# 2_MCU.net
KiCad netlist of a schematic drawn in Altium Designer
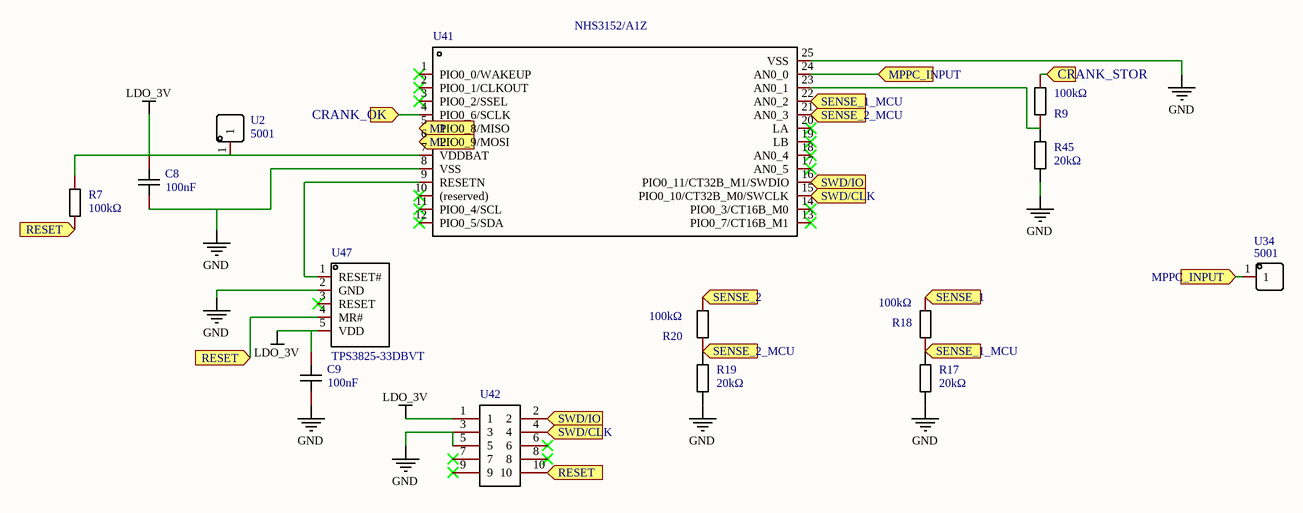
[diagram p0: 2_MCU.schdoc]

(export (version "E")
  (design (tool "Eeschema 10.0.6"))
  (components
    (comp (ref "C8")
      (value "100nF")
      (fields
        (field (name "NAME") "100nF")
        (field (name "MANUFACTURER") "YAGEO")
        (field (name "MANUFACTURER PART") "CC0603KRX7R9BB104")
      )
      (libsource (lib "altium-import") (part "root_3_CC0603KRX7R9BB104_"))
    )
    (comp (ref "C9")
      (value "100nF")
      (fields
        (field (name "NAME") "100nF")
        (field (name "MANUFACTURER") "YAGEO")
        (field (name "MANUFACTURER PART") "CC0603KRX7R9BB104")
      )
      (libsource (lib "altium-import") (part "root_3_CC0603KRX7R9BB104_"))
    )
    (comp (ref "R7")
      (value "100kΩ")
      (fields
        (field (name "MANUFACTURER") "UNI-ROYAL(厚声)")
        (field (name "MANUFACTURER PART") "0603WAF1003T5E")
        (field (name "TOLERANCE") "±1%")
      )
      (libsource (lib "altium-import") (part "root_3_0603WAF1003T5E_"))
    )
    (comp (ref "R9")
      (value "100kΩ")
      (fields
        (field (name "MANUFACTURER") "UNI-ROYAL(厚声)")
        (field (name "MANUFACTURER PART") "0603WAF1003T5E")
        (field (name "TOLERANCE") "±1%")
      )
      (libsource (lib "altium-import") (part "root_1_0603WAF1003T5E_"))
    )
    (comp (ref "R17")
      (value "20kΩ")
      (fields
        (field (name "NAME") "20kΩ")
        (field (name "MANUFACTURER") "UniOhm")
        (field (name "MANUFACTURER PART") "0603WAF2002T5E")
      )
      (libsource (lib "altium-import") (part "root_3_0603WAF2002T5E_"))
    )
    (comp (ref "R18")
      (value "100kΩ")
      (fields
        (field (name "MANUFACTURER") "UNI-ROYAL(厚声)")
        (field (name "MANUFACTURER PART") "0603WAF1003T5E")
        (field (name "TOLERANCE") "±1%")
      )
      (libsource (lib "altium-import") (part "root_1_0603WAF1003T5E_"))
    )
    (comp (ref "R19")
      (value "20kΩ")
      (fields
        (field (name "NAME") "20kΩ")
        (field (name "MANUFACTURER") "UniOhm")
        (field (name "MANUFACTURER PART") "0603WAF2002T5E")
      )
      (libsource (lib "altium-import") (part "root_3_0603WAF2002T5E_"))
    )
    (comp (ref "R20")
      (value "100kΩ")
      (fields
        (field (name "MANUFACTURER") "UNI-ROYAL(厚声)")
        (field (name "MANUFACTURER PART") "0603WAF1003T5E")
        (field (name "TOLERANCE") "±1%")
      )
      (libsource (lib "altium-import") (part "root_1_0603WAF1003T5E_"))
    )
    (comp (ref "R45")
      (value "20kΩ")
      (fields
        (field (name "NAME") "20kΩ")
        (field (name "MANUFACTURER") "UniOhm")
        (field (name "MANUFACTURER PART") "0603WAF2002T5E")
      )
      (libsource (lib "altium-import") (part "root_3_0603WAF2002T5E_"))
    )
    (comp (ref "U2")
      (value "5001")
      (fields (field (name "NAME") "5001") (field (name "MANUFACTURER") "Keystone"))
      (libsource (lib "altium-import") (part "root_1_5001_"))
    )
    (comp (ref "U34")
      (value "5001")
      (fields (field (name "NAME") "5001") (field (name "MANUFACTURER") "Keystone"))
      (libsource (lib "altium-import") (part "root_0_5001_"))
    )
    (comp (ref "U41")
      (value "NHS3152/A1Z")
      (fields (field (name "MANUFACTURER") "NXP(恩智浦)") (field (name "MANUFACTURER PART") "NHS3152/A1Z"))
      (libsource (lib "altium-import") (part "root_0_NHS3152/A1Z_"))
    )
    (comp (ref "U42")
      (value "20021121-00010T4LF")
      (fields (field (name "MANUFACTURER") "Amphenol"))
      (libsource (lib "altium-import") (part "root_3_20021121-00010T4LF_"))
    )
    (comp (ref "U47")
      (value "TPS3825-33DBVT")
      (fields (field (name "MANUFACTURER") "TI(德州仪器)") (field (name "MANUFACTURER PART") "TPS3825-33DBVT"))
      (libsource (lib "altium-import") (part "root_0_TPS3825-33DBVT_"))
    )
  )
  (nets
    (net (code "1") (name "/CRANK_OK") (class "Default")
      (node (ref "U41") (pin "4") (pinfunction "PIO0_6/SCLK_4") (pintype "passive"))
    )
    (net (code "2") (name "/CRANK_STOR") (class "Default")
      (node (ref "R9") (pin "2") (pinfunction "2_2") (pintype "passive"))
    )
    (net (code "3") (name "/M1") (class "Default")
      (node (ref "U41") (pin "5") (pinfunction "PIO0_8/MISO_5") (pintype "passive"))
    )
    (net (code "4") (name "/M2") (class "Default")
      (node (ref "U41") (pin "6") (pinfunction "PIO0_9/MOSI_6") (pintype "passive"))
    )
    (net (code "5") (name "/MPPC_INPUT") (class "Default")
      (node (ref "U34") (pin "1") (pinfunction "1_1") (pintype "passive"))
      (node (ref "U41") (pin "24") (pinfunction "AN0_0_24") (pintype "passive"))
    )
    (net (code "6") (name "/RESET") (class "Default")
      (node (ref "R7") (pin "2") (pinfunction "2_2") (pintype "passive"))
      (node (ref "U42") (pin "10") (pinfunction "10_10") (pintype "passive"))
      (node (ref "U47") (pin "4") (pinfunction "MR#_4") (pintype "passive"))
    )
    (net (code "7") (name "/SENSE_1") (class "Default")
      (node (ref "R18") (pin "2") (pinfunction "2_2") (pintype "passive"))
    )
    (net (code "8") (name "/SENSE_1_MCU") (class "Default")
      (node (ref "R17") (pin "1") (pinfunction "1_1") (pintype "passive"))
      (node (ref "R18") (pin "1") (pinfunction "1_1") (pintype "passive"))
      (node (ref "U41") (pin "22") (pinfunction "AN0_2_22") (pintype "passive"))
    )
    (net (code "9") (name "/SENSE_2") (class "Default")
      (node (ref "R20") (pin "2") (pinfunction "2_2") (pintype "passive"))
    )
    (net (code "10") (name "/SENSE_2_MCU") (class "Default")
      (node (ref "R19") (pin "1") (pinfunction "1_1") (pintype "passive"))
      (node (ref "R20") (pin "1") (pinfunction "1_1") (pintype "passive"))
      (node (ref "U41") (pin "21") (pinfunction "AN0_3_21") (pintype "passive"))
    )
    (net (code "11") (name "/SWD{slash}CLK") (class "Default")
      (node (ref "U41") (pin "15") (pinfunction "PIO0_10/CT32B_M0/SWCLK_15") (pintype "passive"))
      (node (ref "U42") (pin "4") (pinfunction "4_4") (pintype "passive"))
    )
    (net (code "12") (name "/SWD{slash}IO") (class "Default")
      (node (ref "U41") (pin "16") (pinfunction "PIO0_11/CT32B_M1/SWDIO_16") (pintype "passive"))
      (node (ref "U42") (pin "2") (pinfunction "2_2") (pintype "passive"))
    )
    (net (code "13") (name "GND") (class "Default")
      (node (ref "C8") (pin "2") (pinfunction "2_2") (pintype "passive"))
      (node (ref "C9") (pin "2") (pinfunction "2_2") (pintype "passive"))
      (node (ref "R17") (pin "2") (pinfunction "2_2") (pintype "passive"))
      (node (ref "R19") (pin "2") (pinfunction "2_2") (pintype "passive"))
      (node (ref "R45") (pin "2") (pinfunction "2_2") (pintype "passive"))
      (node (ref "U41") (pin "25") (pinfunction "VSS_25") (pintype "passive"))
      (node (ref "U41") (pin "8") (pinfunction "VSS_8") (pintype "passive"))
      (node (ref "U42") (pin "3") (pinfunction "3_3") (pintype "passive"))
      (node (ref "U42") (pin "5") (pinfunction "5_5") (pintype "passive"))
      (node (ref "U47") (pin "2") (pinfunction "GND_2") (pintype "passive"))
    )
    (net (code "14") (name "LDO_3V") (class "Default")
      (node (ref "C8") (pin "1") (pinfunction "1_1") (pintype "passive"))
      (node (ref "C9") (pin "1") (pinfunction "1_1") (pintype "passive"))
      (node (ref "R7") (pin "1") (pinfunction "1_1") (pintype "passive"))
      (node (ref "U2") (pin "1") (pinfunction "1_1") (pintype "passive"))
      (node (ref "U41") (pin "7") (pinfunction "VDDBAT_7") (pintype "passive"))
      (node (ref "U42") (pin "1") (pinfunction "1_1") (pintype "passive"))
      (node (ref "U47") (pin "5") (pinfunction "VDD_5") (pintype "passive"))
    )
    (net (code "15") (name "Net-(U41-AN0_1)") (class "Default")
      (node (ref "R45") (pin "1") (pinfunction "1_1") (pintype "passive"))
      (node (ref "R9") (pin "1") (pinfunction "1_1") (pintype "passive"))
      (node (ref "U41") (pin "23") (pinfunction "AN0_1_23") (pintype "passive"))
    )
    (net (code "16") (name "Net-(U41-RESETN)") (class "Default")
      (node (ref "U41") (pin "9") (pinfunction "RESETN_9") (pintype "passive"))
      (node (ref "U47") (pin "1") (pinfunction "RESET#_1") (pintype "passive"))
    )
    (net (code "17") (name "unconnected-(U41-(reserved)-Pad10)") (class "Default")
      (node (ref "U41") (pin "10") (pinfunction "(reserved)_10") (pintype "passive+no_connect"))
    )
    (net (code "18") (name "unconnected-(U41-AN0_4-Pad18)") (class "Default")
      (node (ref "U41") (pin "18") (pinfunction "AN0_4_18") (pintype "passive+no_connect"))
    )
    (net (code "19") (name "unconnected-(U41-AN0_5-Pad17)") (class "Default")
      (node (ref "U41") (pin "17") (pinfunction "AN0_5_17") (pintype "passive+no_connect"))
    )
    (net (code "20") (name "unconnected-(U41-LA-Pad20)") (class "Default")
      (node (ref "U41") (pin "20") (pinfunction "LA_20") (pintype "passive+no_connect"))
    )
    (net (code "21") (name "unconnected-(U41-LB-Pad19)") (class "Default")
      (node (ref "U41") (pin "19") (pinfunction "LB_19") (pintype "passive+no_connect"))
    )
    (net (code "22") (name "unconnected-(U41-PIO0_0{slash}WAKEUP-Pad1)") (class "Default")
      (node (ref "U41") (pin "1") (pinfunction "PIO0_0/WAKEUP_1") (pintype "passive+no_connect"))
    )
    (net (code "23") (name "unconnected-(U41-PIO0_1{slash}CLKOUT-Pad2)") (class "Default")
      (node (ref "U41") (pin "2") (pinfunction "PIO0_1/CLKOUT_2") (pintype "passive+no_connect"))
    )
    (net (code "24") (name "unconnected-(U41-PIO0_2{slash}SSEL-Pad3)") (class "Default")
      (node (ref "U41") (pin "3") (pinfunction "PIO0_2/SSEL_3") (pintype "passive+no_connect"))
    )
    (net (code "25") (name "unconnected-(U41-PIO0_3{slash}CT16B_M0-Pad14)") (class "Default")
      (node (ref "U41") (pin "14") (pinfunction "PIO0_3/CT16B_M0_14") (pintype "passive+no_connect"))
    )
    (net (code "26") (name "unconnected-(U41-PIO0_4{slash}SCL-Pad11)") (class "Default")
      (node (ref "U41") (pin "11") (pinfunction "PIO0_4/SCL_11") (pintype "passive+no_connect"))
    )
    (net (code "27") (name "unconnected-(U41-PIO0_5{slash}SDA-Pad12)") (class "Default")
      (node (ref "U41") (pin "12") (pinfunction "PIO0_5/SDA_12") (pintype "passive+no_connect"))
    )
    (net (code "28") (name "unconnected-(U41-PIO0_7{slash}CT16B_M1-Pad13)") (class "Default")
      (node (ref "U41") (pin "13") (pinfunction "PIO0_7/CT16B_M1_13") (pintype "passive+no_connect"))
    )
    (net (code "29") (name "unconnected-(U42-Pad6)") (class "Default")
      (node (ref "U42") (pin "6") (pinfunction "6_6") (pintype "passive+no_connect"))
    )
    (net (code "30") (name "unconnected-(U42-Pad7)") (class "Default")
      (node (ref "U42") (pin "7") (pinfunction "7_7") (pintype "passive+no_connect"))
    )
    (net (code "31") (name "unconnected-(U42-Pad8)") (class "Default")
      (node (ref "U42") (pin "8") (pinfunction "8_8") (pintype "passive+no_connect"))
    )
    (net (code "32") (name "unconnected-(U42-Pad9)") (class "Default")
      (node (ref "U42") (pin "9") (pinfunction "9_9") (pintype "passive+no_connect"))
    )
    (net (code "33") (name "unconnected-(U47-RESET-Pad3)") (class "Default")
      (node (ref "U47") (pin "3") (pinfunction "RESET_3") (pintype "passive+no_connect"))
    )
  )
)
